# voltageregulators.net
KiCad netlist of a schematic drawn in EAGLE
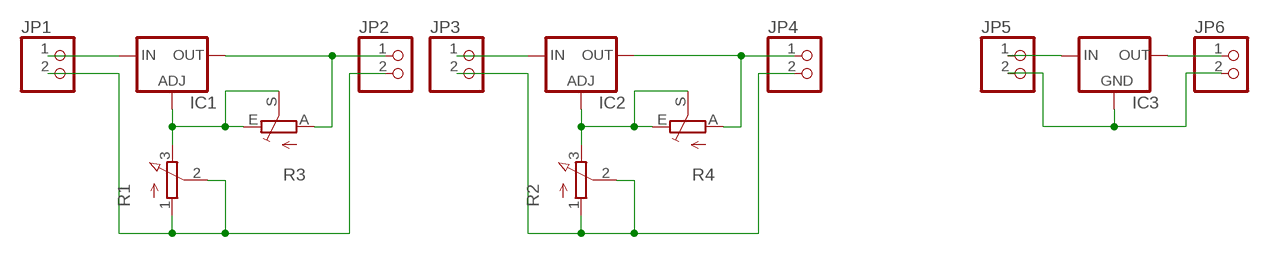
[diagram p0: schematic, sheet 1]

(export (version "E")
  (design (tool "Eeschema 10.0.6"))
  (components
    (comp (ref "IC1")
      (value "LM317TS")
      (footprint "eagle-import:317TS")
      (libsource (lib "eagle-import") (part "LM317TS"))
    )
    (comp (ref "IC2")
      (value "LM317TS")
      (footprint "eagle-import:317TS")
      (libsource (lib "eagle-import") (part "LM317TS"))
    )
    (comp (ref "IC3")
      (value "78XXS")
      (footprint "eagle-import:78XXS")
      (libsource (lib "eagle-import") (part "78XXS"))
    )
    (comp (ref "JP1")
      (value "PINHD-1X2")
      (footprint "eagle-import:1X02")
      (libsource (lib "eagle-import") (part "PINHD-1X2"))
    )
    (comp (ref "JP2")
      (value "PINHD-1X2")
      (footprint "eagle-import:1X02")
      (libsource (lib "eagle-import") (part "PINHD-1X2"))
    )
    (comp (ref "JP3")
      (value "PINHD-1X2")
      (footprint "eagle-import:1X02")
      (libsource (lib "eagle-import") (part "PINHD-1X2"))
    )
    (comp (ref "JP4")
      (value "PINHD-1X2")
      (footprint "eagle-import:1X02")
      (libsource (lib "eagle-import") (part "PINHD-1X2"))
    )
    (comp (ref "JP5")
      (value "PINHD-1X2")
      (footprint "eagle-import:1X02")
      (libsource (lib "eagle-import") (part "PINHD-1X2"))
    )
    (comp (ref "JP6")
      (value "PINHD-1X2")
      (footprint "eagle-import:1X02")
      (libsource (lib "eagle-import") (part "PINHD-1X2"))
    )
    (comp (ref "R1")
      (value "3RP/1610N")
      (footprint "eagle-import:3RP_1610N")
      (libsource (lib "eagle-import") (part "3RP/1610N"))
    )
    (comp (ref "R2")
      (value "3RP/1610N")
      (footprint "eagle-import:3RP_1610N")
      (libsource (lib "eagle-import") (part "3RP/1610N"))
    )
    (comp (ref "R3")
      (value "TRIM_EU-LI10")
      (footprint "eagle-import:LI10")
      (libsource (lib "eagle-import") (part "TRIM_EU-LI10"))
    )
    (comp (ref "R4")
      (value "TRIM_EU-LI10")
      (footprint "eagle-import:LI10")
      (libsource (lib "eagle-import") (part "TRIM_EU-LI10"))
    )
  )
  (nets
    (net (code "1") (name "Net-(IC1-ADJ)") (class "Default")
      (node (ref "IC1") (pin "1") (pinfunction "ADJ_1") (pintype "input"))
      (node (ref "R1") (pin "3") (pinfunction "E_3") (pintype "passive"))
      (node (ref "R3") (pin "E") (pinfunction "E_E") (pintype "passive"))
      (node (ref "R3") (pin "S") (pinfunction "S_S") (pintype "passive"))
    )
    (net (code "2") (name "Net-(IC1-IN)") (class "Default")
      (node (ref "IC1") (pin "3") (pinfunction "IN_3") (pintype "input"))
      (node (ref "JP1") (pin "1") (pinfunction "1_1") (pintype "passive"))
    )
    (net (code "3") (name "Net-(IC1-OUT)") (class "Default")
      (node (ref "IC1") (pin "2") (pinfunction "OUT_2") (pintype "passive"))
      (node (ref "JP2") (pin "1") (pinfunction "1_1") (pintype "passive"))
      (node (ref "R3") (pin "A") (pinfunction "A_A") (pintype "passive"))
    )
    (net (code "4") (name "Net-(IC2-ADJ)") (class "Default")
      (node (ref "IC2") (pin "1") (pinfunction "ADJ_1") (pintype "input"))
      (node (ref "R2") (pin "3") (pinfunction "E_3") (pintype "passive"))
      (node (ref "R4") (pin "E") (pinfunction "E_E") (pintype "passive"))
      (node (ref "R4") (pin "S") (pinfunction "S_S") (pintype "passive"))
    )
    (net (code "5") (name "Net-(IC2-IN)") (class "Default")
      (node (ref "IC2") (pin "3") (pinfunction "IN_3") (pintype "input"))
      (node (ref "JP3") (pin "1") (pinfunction "1_1") (pintype "passive"))
    )
    (net (code "6") (name "Net-(IC2-OUT)") (class "Default")
      (node (ref "IC2") (pin "2") (pinfunction "OUT_2") (pintype "passive"))
      (node (ref "JP4") (pin "1") (pinfunction "1_1") (pintype "passive"))
      (node (ref "R4") (pin "A") (pinfunction "A_A") (pintype "passive"))
    )
    (net (code "7") (name "Net-(IC3-PadGND)") (class "Default")
      (node (ref "IC3") (pin "GND") (pinfunction "GND_GND") (pintype "input"))
      (node (ref "JP5") (pin "2") (pinfunction "2_2") (pintype "passive"))
      (node (ref "JP6") (pin "2") (pinfunction "2_2") (pintype "passive"))
    )
    (net (code "8") (name "Net-(IC3-PadIN)") (class "Default")
      (node (ref "IC3") (pin "IN") (pinfunction "IN_IN") (pintype "input"))
      (node (ref "JP5") (pin "1") (pinfunction "1_1") (pintype "passive"))
    )
    (net (code "9") (name "Net-(IC3-PadOUT)") (class "Default")
      (node (ref "IC3") (pin "OUT") (pinfunction "OUT_OUT") (pintype "passive"))
      (node (ref "JP6") (pin "1") (pinfunction "1_1") (pintype "passive"))
    )
    (net (code "10") (name "Net-(R1-A)") (class "Default")
      (node (ref "JP1") (pin "2") (pinfunction "2_2") (pintype "passive"))
      (node (ref "JP2") (pin "2") (pinfunction "2_2") (pintype "passive"))
      (node (ref "R1") (pin "1") (pinfunction "A_1") (pintype "passive"))
      (node (ref "R1") (pin "2") (pinfunction "S_2") (pintype "passive"))
    )
    (net (code "11") (name "Net-(R2-A)") (class "Default")
      (node (ref "JP3") (pin "2") (pinfunction "2_2") (pintype "passive"))
      (node (ref "JP4") (pin "2") (pinfunction "2_2") (pintype "passive"))
      (node (ref "R2") (pin "1") (pinfunction "A_1") (pintype "passive"))
      (node (ref "R2") (pin "2") (pinfunction "S_2") (pintype "passive"))
    )
  )
)
